# Gas_Sampler-3_3V_LDO.net
KiCad netlist of a schematic drawn in Altium Designer
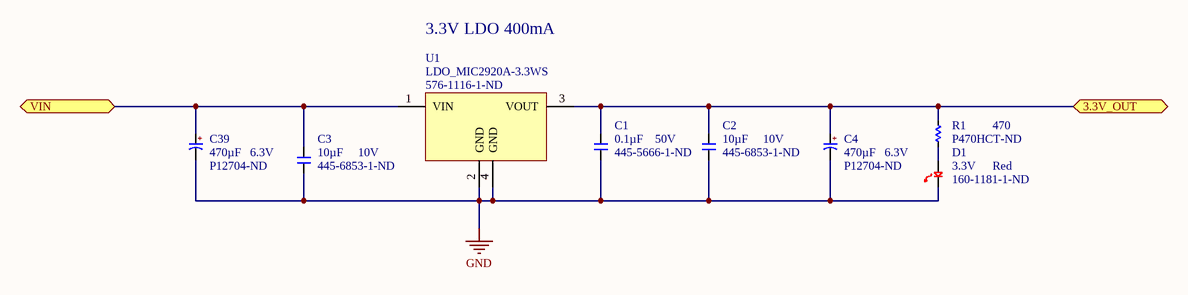
[diagram p0: Gas_Sampler-3.3V_LDO.SchDoc]

(export (version "E")
  (design (tool "Eeschema 10.0.6"))
  (components
    (comp (ref "C1")
      (value "0.1µF")
      (footprint "C0603")
      (description "CAP CER 0.1UF 50V 10% X7R 0603")
      (fields
        (field (name "MANUFACTURER") "TDK Corporation")
        (field (name "MANUFACTURER PART NUMBER") "CGA3E2X7R1H104K080AA")
        (field (name "VOLTAGE - RATED") "50V")
        (field (name "SUPPLIER PART NUMBER 1") "445-5666-1-ND")
      )
      (libsource (lib "capacitor") (part "CAP_CER_0603_0.1UF_50V_10%_X7R"))
    )
    (comp (ref "C2")
      (value "10µF")
      (footprint "C0603")
      (description "CAP CER 10UF 10V X5R 0603")
      (fields
        (field (name "MANUFACTURER") "TDK Corporation")
        (field (name "MANUFACTURER PART NUMBER") "C1608X5R1A106M080AC")
        (field (name "VOLTAGE - RATED") "10V")
        (field (name "SUPPLIER PART NUMBER 1") "445-6853-1-ND")
      )
      (libsource (lib "capacitor") (part "CAP_CER_0603_10UF_10V_20%_X5R"))
    )
    (comp (ref "C3")
      (value "10µF")
      (footprint "C0603")
      (description "CAP CER 10UF 10V X5R 0603")
      (fields
        (field (name "MANUFACTURER") "TDK Corporation")
        (field (name "MANUFACTURER PART NUMBER") "C1608X5R1A106M080AC")
        (field (name "VOLTAGE - RATED") "10V")
        (field (name "SUPPLIER PART NUMBER 1") "445-6853-1-ND")
      )
      (libsource (lib "capacitor") (part "CAP_CER_0603_10UF_10V_20%_X5R"))
    )
    (comp (ref "C4")
      (value "470µF")
      (footprint "CAP_RADIAL_8MM_DIA_11.5MM_LEN_3.5MM_LEADSPACE")
      (description "CAP ALUM 470UF 6.3V 20% RADIAL")
      (fields
        (field (name "MANUFACTURER") "Panasonic Electronic Components")
        (field (name "MANUFACTURER PART NUMBER") "EEU-FC0J471")
        (field (name "VOLTAGE - RATED") "6.3V")
        (field (name "SUPPLIER PART NUMBER 1") "P12704-ND")
      )
      (libsource (lib "capacitor") (part "CAP_ALUM_470UF_6.3V_20%_RADIAL_8X11.5MM"))
    )
    (comp (ref "C39")
      (value "470µF")
      (footprint "CAP_RADIAL_8MM_DIA_11.5MM_LEN_3.5MM_LEADSPACE")
      (description "CAP ALUM 470UF 6.3V 20% RADIAL")
      (fields
        (field (name "MANUFACTURER") "Panasonic Electronic Components")
        (field (name "MANUFACTURER PART NUMBER") "EEU-FC0J471")
        (field (name "VOLTAGE - RATED") "6.3V")
        (field (name "SUPPLIER PART NUMBER 1") "P12704-ND")
      )
      (libsource (lib "capacitor") (part "CAP_ALUM_470UF_6.3V_20%_RADIAL_8X11.5MM"))
    )
    (comp (ref "D1")
      (value "3.3V")
      (footprint "LED_0603_RED")
      (description "LED RED CLEAR 0603 SMD")
      (fields
        (field (name "MANUFACTURER") "Lite-On Inc")
        (field (name "MANUFACTURER PART NUMBER") "LTST-C190CKT")
        (field (name "SUPPLIER PART NUMBER 1") "160-1181-1-ND")
        (field (name "COLOR") "Red")
      )
      (libsource (lib "diode") (part "LED_0603_RED_LR_LTST-C190CKT"))
    )
    (comp (ref "R1")
      (value "470")
      (footprint "R0603")
      (description "RES 470 OHM 1/10W 1% 0603 SMD")
      (fields
        (field (name "MANUFACTURER") "Panasonic Electronic Components")
        (field (name "MANUFACTURER PART NUMBER") "ERJ-3EKF4700V")
        (field (name "SUPPLIER PART NUMBER 1") "P470HCT-ND")
      )
      (libsource (lib "resistor") (part "RES_0603_470_OHM_1/10W_1%"))
    )
    (comp (ref "U1")
      (value "LDO_MIC2920A-3.3WS")
      (footprint "4SOT223")
      (description "IC REG LDO 3.3V 0.4A SOT223")
      (fields
        (field (name "MANUFACTURER") "Microchip Technology")
        (field (name "MANUFACTURER PART NUMBER") "MIC2920A-3.3WS-TR")
        (field (name "SUPPLIER PART NUMBER 1") "576-1116-1-ND")
      )
      (libsource (lib "ic_pmic") (part "LDO_MIC2920A-3.3WS"))
    )
  )
  (nets
    (net (code "1") (name "/3.3V_OUT") (class "Default")
      (node (ref "C1") (pin "1") (pintype "passive"))
      (node (ref "C2") (pin "1") (pintype "passive"))
      (node (ref "C4") (pin "1") (pintype "passive"))
      (node (ref "R1") (pin "2") (pintype "passive"))
      (node (ref "U1") (pin "3") (pinfunction "VOUT_3") (pintype "passive"))
    )
    (net (code "2") (name "/VIN") (class "Default")
      (node (ref "C3") (pin "1") (pintype "passive"))
      (node (ref "C39") (pin "1") (pintype "passive"))
      (node (ref "U1") (pin "1") (pinfunction "VIN_1") (pintype "passive"))
    )
    (net (code "3") (name "GND") (class "Default")
      (node (ref "C1") (pin "2") (pintype "passive"))
      (node (ref "C2") (pin "2") (pintype "passive"))
      (node (ref "C3") (pin "2") (pintype "passive"))
      (node (ref "C39") (pin "2") (pintype "passive"))
      (node (ref "C4") (pin "2") (pintype "passive"))
      (node (ref "D1") (pin "2") (pinfunction "CATHODE_2") (pintype "passive"))
      (node (ref "U1") (pin "2") (pinfunction "GND_2") (pintype "passive"))
      (node (ref "U1") (pin "4") (pinfunction "GND_4") (pintype "passive"))
    )
    (net (code "4") (name "Net-(D1-ANODE)") (class "Default")
      (node (ref "D1") (pin "1") (pinfunction "ANODE_1") (pintype "passive"))
      (node (ref "R1") (pin "1") (pintype "passive"))
    )
  )
)
